# uart_key.net
KiCad netlist of a schematic drawn in Altium Designer
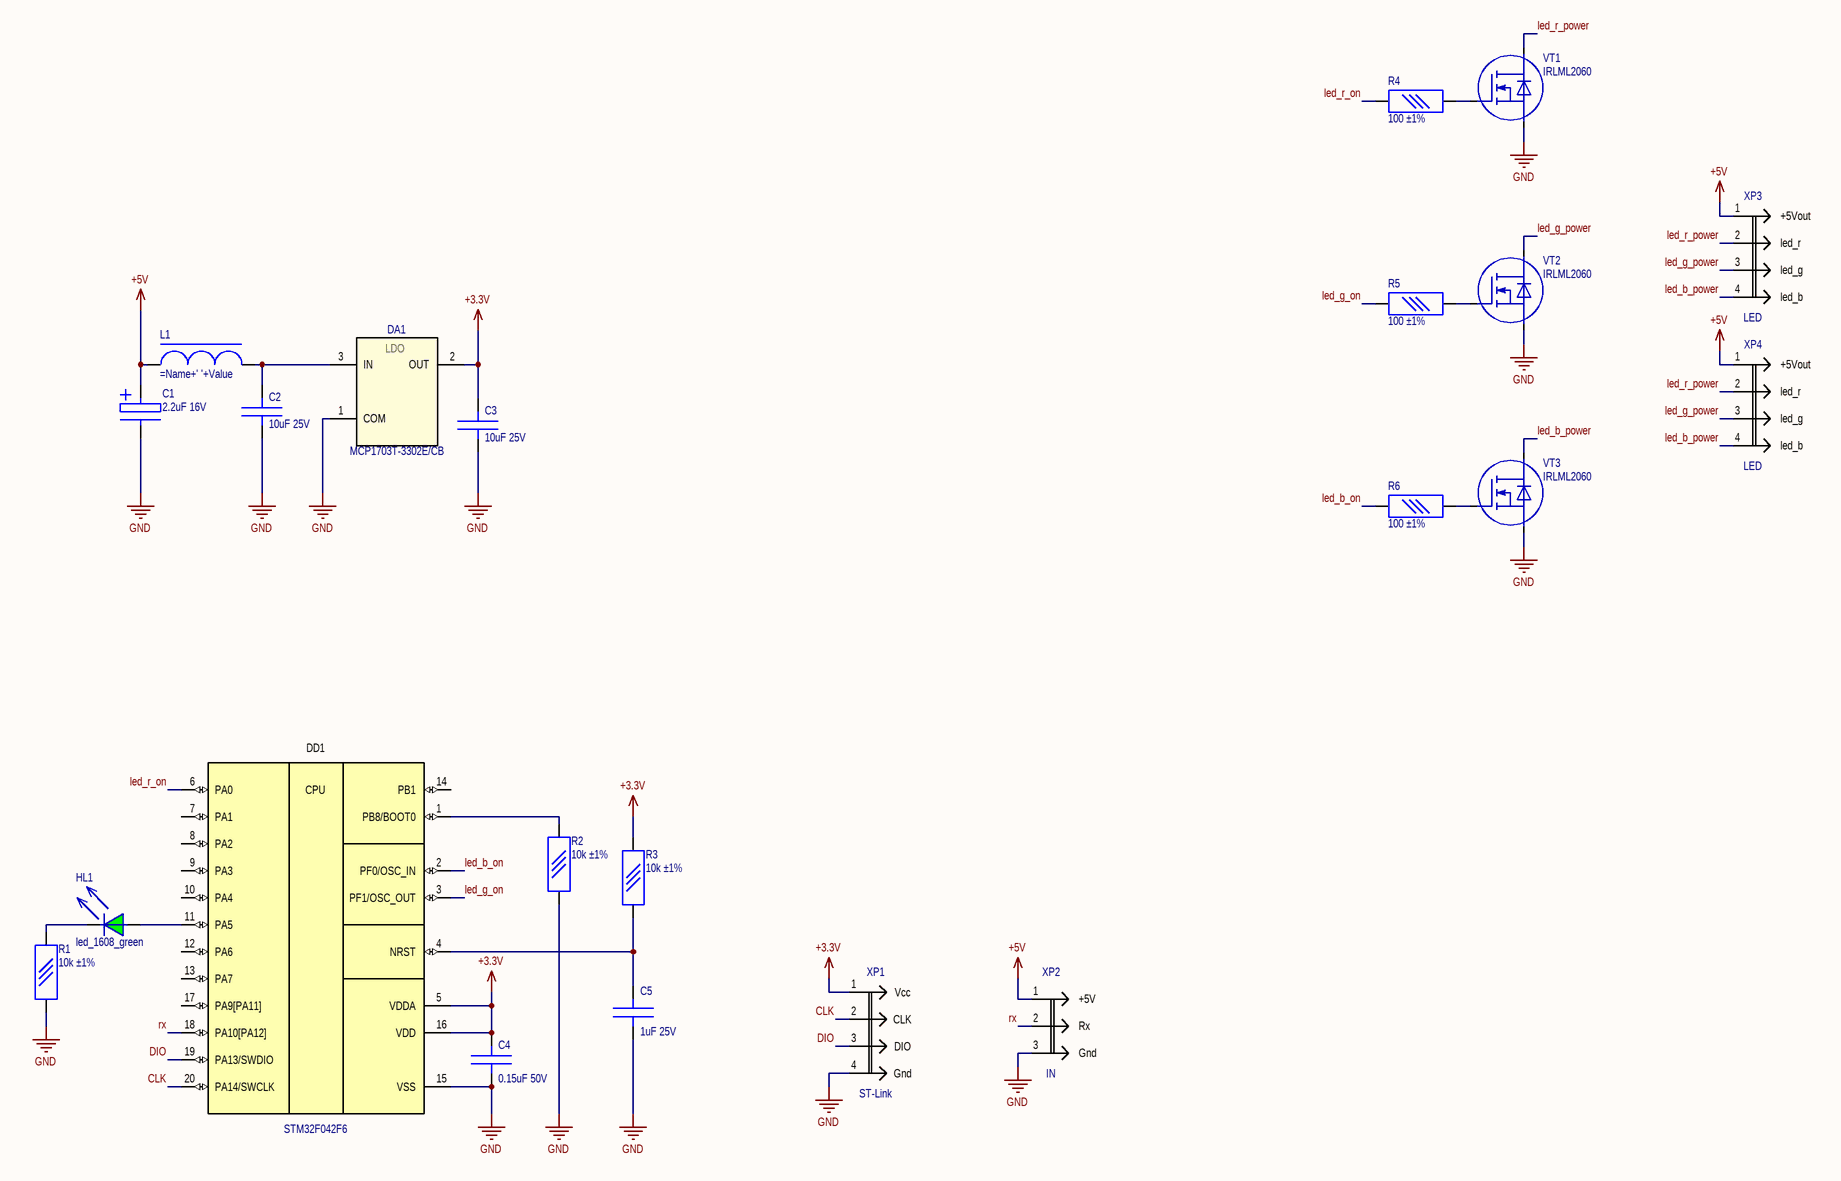
[diagram p0: uart_key.SchDoc]

(export (version "E")
  (design (tool "Eeschema 10.0.6"))
  (components
    (comp (ref "C1")
      (value "2.2uF 16V")
      (footprint "TANT_3.2X1.6_A")
      (fields (field (name "VOLTAGE") "16V") (field (name "TOLERANCE") "±10%"))
      (libsource (lib "AD_lib") (part "Capacitor_elec"))
    )
    (comp (ref "C2")
      (value "10uF 25V")
      (footprint "CC0603_0.8mm")
      (fields (field (name "VOLTAGE") "25V") (field (name "TOLERANCE") "±10%"))
      (libsource (lib "AD_lib") (part "Capacitor"))
    )
    (comp (ref "C3")
      (value "10uF 25V")
      (footprint "CC0603_0.8mm")
      (fields (field (name "VOLTAGE") "25V") (field (name "TOLERANCE") "±10%"))
      (libsource (lib "AD_lib") (part "Capacitor"))
    )
    (comp (ref "C4")
      (value "0.15uF 50V")
      (footprint "CC0603_0.8mm")
      (fields (field (name "VOLTAGE") "50V") (field (name "TOLERANCE") "±10%"))
      (libsource (lib "AD_lib") (part "Capacitor"))
    )
    (comp (ref "C5")
      (value "1uF 25V")
      (footprint "CC0603_0.8mm")
      (fields (field (name "VOLTAGE") "25V") (field (name "TOLERANCE") "±10%"))
      (libsource (lib "AD_lib") (part "Capacitor"))
    )
    (comp (ref "DA1")
      (value "MCP1703T-3302E/CB")
      (footprint "SOT-23A_MCP")
      (libsource (lib "AD_lib") (part "MCP1703T-3302E/CB"))
    )
    (comp (ref "DD1")
      (value "STM32F042F6")
      (footprint "TSSOP-20_ST")
      (libsource (lib "AD_lib") (part "STM32F042F6"))
    )
    (comp (ref "HL1")
      (value "led_1608_green")
      (footprint "led_1608")
      (libsource (lib "AD_lib") (part "led_1608_green"))
    )
    (comp (ref "L1") (value "15uH") (footprint "LQH43C") (libsource (lib "AD_lib") (part "Inductor")))
    (comp (ref "R1")
      (value "10k ±1%")
      (footprint "R0603")
      (fields (field (name "TOLERANCE") "±1%"))
      (libsource (lib "AD_lib") (part "Res_0603"))
    )
    (comp (ref "R2")
      (value "10k ±1%")
      (footprint "R0603")
      (fields (field (name "TOLERANCE") "±1%"))
      (libsource (lib "AD_lib") (part "Res_0603"))
    )
    (comp (ref "R3")
      (value "10k ±1%")
      (footprint "R0603")
      (fields (field (name "TOLERANCE") "±1%"))
      (libsource (lib "AD_lib") (part "Res_0603"))
    )
    (comp (ref "R4")
      (value "100 ±1%")
      (footprint "R0603")
      (fields (field (name "TOLERANCE") "±1%"))
      (libsource (lib "AD_lib") (part "Res_0603"))
    )
    (comp (ref "R5")
      (value "100 ±1%")
      (footprint "R0603")
      (fields (field (name "TOLERANCE") "±1%"))
      (libsource (lib "AD_lib") (part "Res_0603"))
    )
    (comp (ref "R6")
      (value "100 ±1%")
      (footprint "R0603")
      (fields (field (name "TOLERANCE") "±1%"))
      (libsource (lib "AD_lib") (part "Res_0603"))
    )
    (comp (ref "VT1") (value "IRLML2060") (footprint "SOT-23") (libsource (lib "AD_lib") (part "IRLML2060")))
    (comp (ref "VT2") (value "IRLML2060") (footprint "SOT-23") (libsource (lib "AD_lib") (part "IRLML2060")))
    (comp (ref "VT3") (value "IRLML2060") (footprint "SOT-23") (libsource (lib "AD_lib") (part "IRLML2060")))
    (comp (ref "XP1")
      (value "ST-Link")
      (footprint "B4B-ZR")
      (fields
        (field (name "CIRCUIT_1") "Vcc")
        (field (name "CIRCUIT_2") "CLK")
        (field (name "CIRCUIT_3") "DIO")
        (field (name "CIRCUIT_4") "Gnd")
      )
      (libsource (lib "AD_lib") (part "B4B-ZR_conn_01x04_st_link"))
    )
    (comp (ref "XP2")
      (value "IN")
      (footprint "JST_XH_B3B-XH-A_1x03_P2.50mm_Vertical")
      (fields
        (field (name "CIRCUIT_1") "+5V")
        (field (name "CIRCUIT_2") "Rx")
        (field (name "CIRCUIT_3") "Gnd")
      )
      (libsource (lib "AD_lib") (part "JST_XH_B3B-XH-A_1x04_P2.50mm_Vertical_1"))
    )
    (comp (ref "XP3")
      (value "LED")
      (footprint "JST_XH_B4B-XH-A_1x04_P2.50mm_Vertical")
      (fields
        (field (name "CIRCUIT_1") "+5Vout")
        (field (name "CIRCUIT_2") "led_r")
        (field (name "CIRCUIT_3") "led_g")
        (field (name "CIRCUIT_4") "led_b")
      )
      (libsource (lib "AD_lib") (part "JST_XH_B4B-XH-A_1x04_P2.50mm_Vertical"))
    )
    (comp (ref "XP4")
      (value "LED")
      (footprint "JST_XH_B4B-XH-A_1x04_P2.50mm_Vertical")
      (fields
        (field (name "CIRCUIT_1") "+5Vout")
        (field (name "CIRCUIT_2") "led_r")
        (field (name "CIRCUIT_3") "led_g")
        (field (name "CIRCUIT_4") "led_b")
      )
      (libsource (lib "AD_lib") (part "JST_XH_B4B-XH-A_1x04_P2.50mm_Vertical"))
    )
  )
  (nets
    (net (code "1") (name "+3.3V") (class "Default")
      (node (ref "C3") (pin "1") (pintype "passive"))
      (node (ref "C4") (pin "1") (pintype "passive"))
      (node (ref "DA1") (pin "2") (pinfunction "OUT_2") (pintype "passive"))
      (node (ref "DD1") (pin "16") (pinfunction "VDD_16") (pintype "power_in"))
      (node (ref "DD1") (pin "5") (pinfunction "VDDA_5") (pintype "power_in"))
      (node (ref "R3") (pin "1") (pinfunction "BOT_1") (pintype "passive"))
      (node (ref "XP1") (pin "1") (pinfunction "1_1") (pintype "passive"))
    )
    (net (code "2") (name "+5V") (class "Default")
      (node (ref "C1") (pin "2") (pinfunction "+_2") (pintype "passive"))
      (node (ref "L1") (pin "1") (pintype "passive"))
      (node (ref "XP2") (pin "1") (pinfunction "1_1") (pintype "passive"))
      (node (ref "XP3") (pin "1") (pinfunction "1_1") (pintype "passive"))
      (node (ref "XP4") (pin "1") (pinfunction "1_1") (pintype "passive"))
    )
    (net (code "3") (name "/CLK") (class "Default")
      (node (ref "DD1") (pin "20") (pinfunction "PA14/SWCLK_20") (pintype "bidirectional"))
      (node (ref "XP1") (pin "2") (pinfunction "2_2") (pintype "passive"))
    )
    (net (code "4") (name "/DIO") (class "Default")
      (node (ref "DD1") (pin "19") (pinfunction "PA13/SWDIO_19") (pintype "bidirectional"))
      (node (ref "XP1") (pin "3") (pinfunction "3_3") (pintype "passive"))
    )
    (net (code "5") (name "/led_b_on") (class "Default")
      (node (ref "DD1") (pin "2") (pinfunction "PF0/OSC_IN_2") (pintype "bidirectional"))
      (node (ref "R6") (pin "1") (pinfunction "BOT_1") (pintype "passive"))
    )
    (net (code "6") (name "/led_b_power") (class "Default")
      (node (ref "VT3") (pin "3") (pinfunction "D_3") (pintype "passive"))
      (node (ref "XP3") (pin "4") (pinfunction "4_4") (pintype "passive"))
      (node (ref "XP4") (pin "4") (pinfunction "4_4") (pintype "passive"))
    )
    (net (code "7") (name "/led_g_on") (class "Default")
      (node (ref "DD1") (pin "3") (pinfunction "PF1/OSC_OUT_3") (pintype "bidirectional"))
      (node (ref "R5") (pin "1") (pinfunction "BOT_1") (pintype "passive"))
    )
    (net (code "8") (name "/led_g_power") (class "Default")
      (node (ref "VT2") (pin "3") (pinfunction "D_3") (pintype "passive"))
      (node (ref "XP3") (pin "3") (pinfunction "3_3") (pintype "passive"))
      (node (ref "XP4") (pin "3") (pinfunction "3_3") (pintype "passive"))
    )
    (net (code "9") (name "/led_r_on") (class "Default")
      (node (ref "DD1") (pin "6") (pinfunction "PA0_6") (pintype "bidirectional"))
      (node (ref "R4") (pin "1") (pinfunction "BOT_1") (pintype "passive"))
    )
    (net (code "10") (name "/led_r_power") (class "Default")
      (node (ref "VT1") (pin "3") (pinfunction "D_3") (pintype "passive"))
      (node (ref "XP3") (pin "2") (pinfunction "2_2") (pintype "passive"))
      (node (ref "XP4") (pin "2") (pinfunction "2_2") (pintype "passive"))
    )
    (net (code "11") (name "/rx") (class "Default")
      (node (ref "DD1") (pin "18") (pinfunction "PA10[PA12]_18") (pintype "bidirectional"))
      (node (ref "XP2") (pin "2") (pinfunction "2_2") (pintype "passive"))
    )
    (net (code "12") (name "GND") (class "Default")
      (node (ref "C1") (pin "1") (pinfunction "-_1") (pintype "passive"))
      (node (ref "C2") (pin "2") (pintype "passive"))
      (node (ref "C3") (pin "2") (pintype "passive"))
      (node (ref "C4") (pin "2") (pintype "passive"))
      (node (ref "C5") (pin "2") (pintype "passive"))
      (node (ref "DA1") (pin "1") (pinfunction "COM_1") (pintype "passive"))
      (node (ref "DD1") (pin "15") (pinfunction "VSS_15") (pintype "power_in"))
      (node (ref "R1") (pin "2") (pinfunction "TOP_2") (pintype "passive"))
      (node (ref "R2") (pin "1") (pinfunction "BOT_1") (pintype "passive"))
      (node (ref "VT1") (pin "2") (pinfunction "S_2") (pintype "passive"))
      (node (ref "VT2") (pin "2") (pinfunction "S_2") (pintype "passive"))
      (node (ref "VT3") (pin "2") (pinfunction "S_2") (pintype "passive"))
      (node (ref "XP1") (pin "4") (pinfunction "4_4") (pintype "passive"))
      (node (ref "XP2") (pin "3") (pinfunction "3_3") (pintype "passive"))
    )
    (net (code "13") (name "Net-(DA1-IN)") (class "Default")
      (node (ref "C2") (pin "1") (pintype "passive"))
      (node (ref "DA1") (pin "3") (pinfunction "IN_3") (pintype "passive"))
      (node (ref "L1") (pin "2") (pintype "passive"))
    )
    (net (code "14") (name "Net-(DD1-NRST)") (class "Default")
      (node (ref "C5") (pin "1") (pintype "passive"))
      (node (ref "DD1") (pin "4") (pinfunction "NRST_4") (pintype "bidirectional"))
      (node (ref "R3") (pin "2") (pinfunction "TOP_2") (pintype "passive"))
    )
    (net (code "15") (name "Net-(DD1-PA5)") (class "Default")
      (node (ref "DD1") (pin "11") (pinfunction "PA5_11") (pintype "bidirectional"))
      (node (ref "HL1") (pin "2") (pinfunction "A_2") (pintype "passive"))
    )
    (net (code "16") (name "Net-(DD1-PB8{slash}BOOT0)") (class "Default")
      (node (ref "DD1") (pin "1") (pinfunction "PB8/BOOT0_1") (pintype "bidirectional"))
      (node (ref "R2") (pin "2") (pinfunction "TOP_2") (pintype "passive"))
    )
    (net (code "17") (name "Net-(HL1-C)") (class "Default")
      (node (ref "HL1") (pin "1") (pinfunction "C_1") (pintype "passive"))
      (node (ref "R1") (pin "1") (pinfunction "BOT_1") (pintype "passive"))
    )
    (net (code "18") (name "Net-(R4-TOP)") (class "Default")
      (node (ref "R4") (pin "2") (pinfunction "TOP_2") (pintype "passive"))
      (node (ref "VT1") (pin "1") (pinfunction "G_1") (pintype "passive"))
    )
    (net (code "19") (name "Net-(R5-TOP)") (class "Default")
      (node (ref "R5") (pin "2") (pinfunction "TOP_2") (pintype "passive"))
      (node (ref "VT2") (pin "1") (pinfunction "G_1") (pintype "passive"))
    )
    (net (code "20") (name "Net-(R6-TOP)") (class "Default")
      (node (ref "R6") (pin "2") (pinfunction "TOP_2") (pintype "passive"))
      (node (ref "VT3") (pin "1") (pinfunction "G_1") (pintype "passive"))
    )
    (net (code "21") (name "unconnected-(DD1-PA1-Pad7)") (class "Default")
      (node (ref "DD1") (pin "7") (pinfunction "PA1_7") (pintype "bidirectional"))
    )
    (net (code "22") (name "unconnected-(DD1-PA2-Pad8)") (class "Default")
      (node (ref "DD1") (pin "8") (pinfunction "PA2_8") (pintype "bidirectional"))
    )
    (net (code "23") (name "unconnected-(DD1-PA3-Pad9)") (class "Default")
      (node (ref "DD1") (pin "9") (pinfunction "PA3_9") (pintype "bidirectional"))
    )
    (net (code "24") (name "unconnected-(DD1-PA4-Pad10)") (class "Default")
      (node (ref "DD1") (pin "10") (pinfunction "PA4_10") (pintype "bidirectional"))
    )
    (net (code "25") (name "unconnected-(DD1-PA6-Pad12)") (class "Default")
      (node (ref "DD1") (pin "12") (pinfunction "PA6_12") (pintype "bidirectional"))
    )
    (net (code "26") (name "unconnected-(DD1-PA7-Pad13)") (class "Default")
      (node (ref "DD1") (pin "13") (pinfunction "PA7_13") (pintype "bidirectional"))
    )
    (net (code "27") (name "unconnected-(DD1-PA9[PA11]-Pad17)") (class "Default")
      (node (ref "DD1") (pin "17") (pinfunction "PA9[PA11]_17") (pintype "bidirectional"))
    )
    (net (code "28") (name "unconnected-(DD1-PB1-Pad14)") (class "Default")
      (node (ref "DD1") (pin "14") (pinfunction "PB1_14") (pintype "bidirectional"))
    )
  )
)
